# TinyTony_ShenzenReady.net
KiCad netlist of a schematic drawn in EAGLE
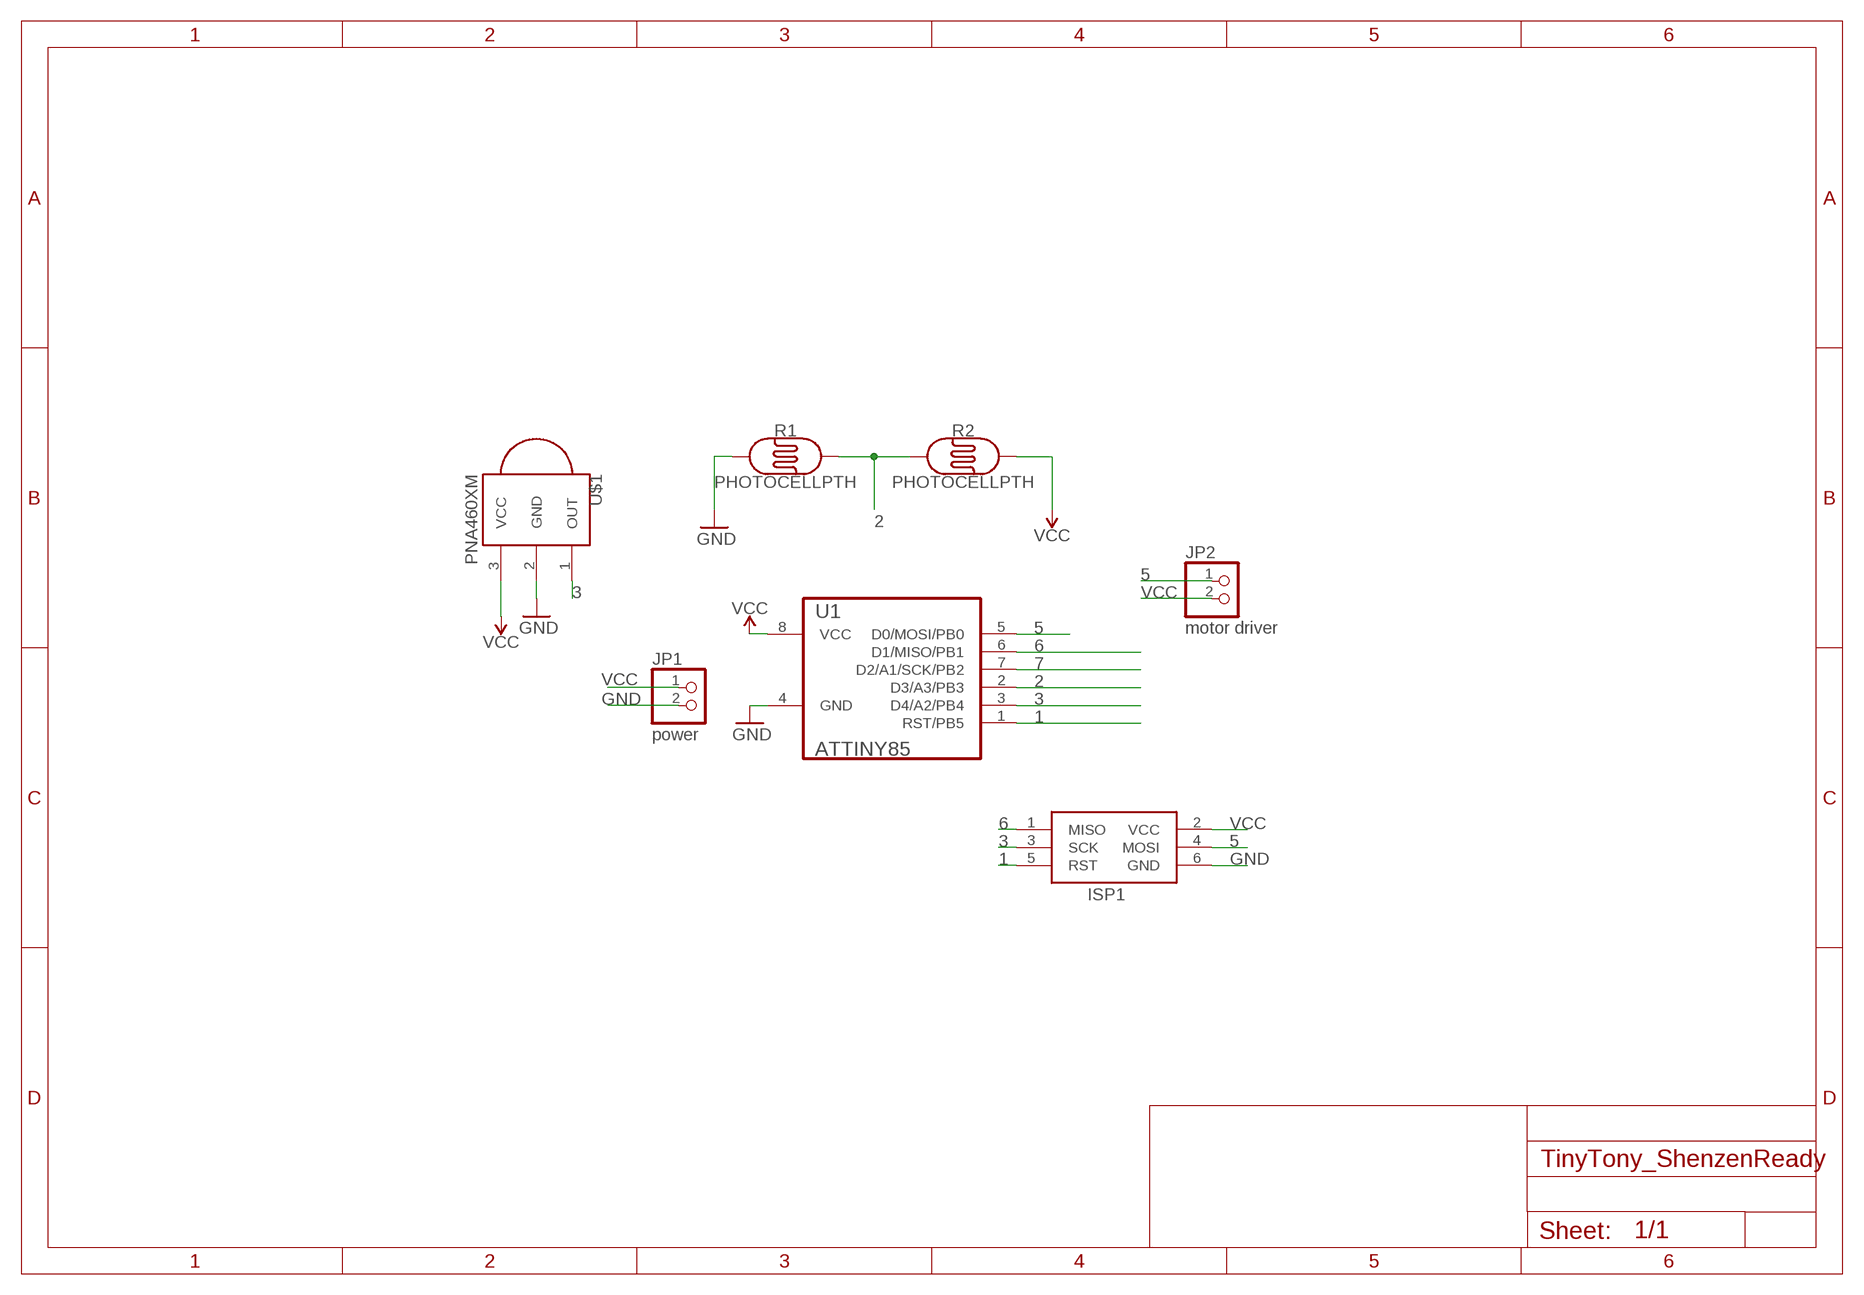
[diagram p0: schematic, sheet 1]

(export (version "E")
  (design (tool "Eeschema 10.0.6"))
  (components
    (comp (ref "ISP1")
      (value "AVRISPPOGO")
      (footprint "eagle-import:AVRISP-50MIL")
      (libsource (lib "eagle-import") (part "AVRISPPOGO"))
    )
    (comp (ref "JP1")
      (value "power")
      (footprint "eagle-import:1X02_ROUND")
      (libsource (lib "eagle-import") (part "HEADER-1X2ROUND"))
    )
    (comp (ref "JP2")
      (value "motor driver")
      (footprint "eagle-import:1X02_ROUND")
      (libsource (lib "eagle-import") (part "HEADER-1X2ROUND"))
    )
    (comp (ref "R1")
      (value "PHOTOCELLPTH")
      (footprint "eagle-import:PHOTOCELL")
      (libsource (lib "eagle-import") (part "PHOTOCELLPTH"))
    )
    (comp (ref "R2")
      (value "PHOTOCELLPTH")
      (footprint "eagle-import:PHOTOCELL")
      (libsource (lib "eagle-import") (part "PHOTOCELLPTH"))
    )
    (comp (ref "U$1")
      (value "PNA460XM")
      (footprint "eagle-import:PNA460XM")
      (libsource (lib "eagle-import") (part "PNA460XM"))
    )
    (comp (ref "U1")
      (value "ATTINY85")
      (footprint "eagle-import:SOIC127P798X216-8N")
      (fields (field (name "MPN") "ATTINY85-20SU"))
      (libsource (lib "eagle-import") (part "ATTINY85-20SU"))
    )
  )
  (nets
    (net (code "1") (name "/1") (class "Default")
      (node (ref "ISP1") (pin "5") (pinfunction "RST_5") (pintype "output"))
      (node (ref "U1") (pin "1") (pinfunction "RST/PB5_1") (pintype "bidirectional"))
    )
    (net (code "2") (name "/2") (class "Default")
      (node (ref "R1") (pin "2") (pinfunction "P$2_2") (pintype "bidirectional"))
      (node (ref "R2") (pin "1") (pinfunction "P$1_1") (pintype "bidirectional"))
      (node (ref "U1") (pin "2") (pinfunction "D3/A3/PB3_2") (pintype "bidirectional"))
    )
    (net (code "3") (name "/3") (class "Default")
      (node (ref "ISP1") (pin "3") (pinfunction "SCK_3") (pintype "output"))
      (node (ref "U$1") (pin "1") (pinfunction "OUT_1") (pintype "output"))
      (node (ref "U1") (pin "3") (pinfunction "D4/A2/PB4_3") (pintype "bidirectional"))
    )
    (net (code "4") (name "/5") (class "Default")
      (node (ref "ISP1") (pin "4") (pinfunction "MOSI_4") (pintype "output"))
      (node (ref "JP2") (pin "1") (pinfunction "1_1") (pintype "passive"))
      (node (ref "U1") (pin "5") (pinfunction "D0/MOSI/PB0_5") (pintype "bidirectional"))
    )
    (net (code "5") (name "/6") (class "Default")
      (node (ref "ISP1") (pin "1") (pinfunction "MISO_1") (pintype "input"))
      (node (ref "U1") (pin "6") (pinfunction "D1/MISO/PB1_6") (pintype "bidirectional"))
    )
    (net (code "6") (name "/7") (class "Default")
      (node (ref "U1") (pin "7") (pinfunction "D2/A1/SCK/PB2_7") (pintype "bidirectional"))
    )
    (net (code "7") (name "GND") (class "Default")
      (node (ref "ISP1") (pin "6") (pinfunction "GND_6") (pintype "power_in"))
      (node (ref "JP1") (pin "2") (pinfunction "2_2") (pintype "passive"))
      (node (ref "R1") (pin "1") (pinfunction "P$1_1") (pintype "bidirectional"))
      (node (ref "U$1") (pin "2") (pinfunction "GND_2") (pintype "power_in"))
      (node (ref "U1") (pin "4") (pinfunction "GND_4") (pintype "passive"))
    )
    (net (code "8") (name "VCC") (class "Default")
      (node (ref "ISP1") (pin "2") (pinfunction "VCC_2") (pintype "power_in"))
      (node (ref "JP1") (pin "1") (pinfunction "1_1") (pintype "passive"))
      (node (ref "JP2") (pin "2") (pinfunction "2_2") (pintype "passive"))
      (node (ref "R2") (pin "2") (pinfunction "P$2_2") (pintype "bidirectional"))
      (node (ref "U$1") (pin "3") (pinfunction "VCC_3") (pintype "power_in"))
      (node (ref "U1") (pin "8") (pinfunction "VCC_8") (pintype "power_in"))
    )
  )
)
